# SCH_Bed_sensor_2021-08-20.net
KiCad netlist of a schematic drawn in EasyEDA
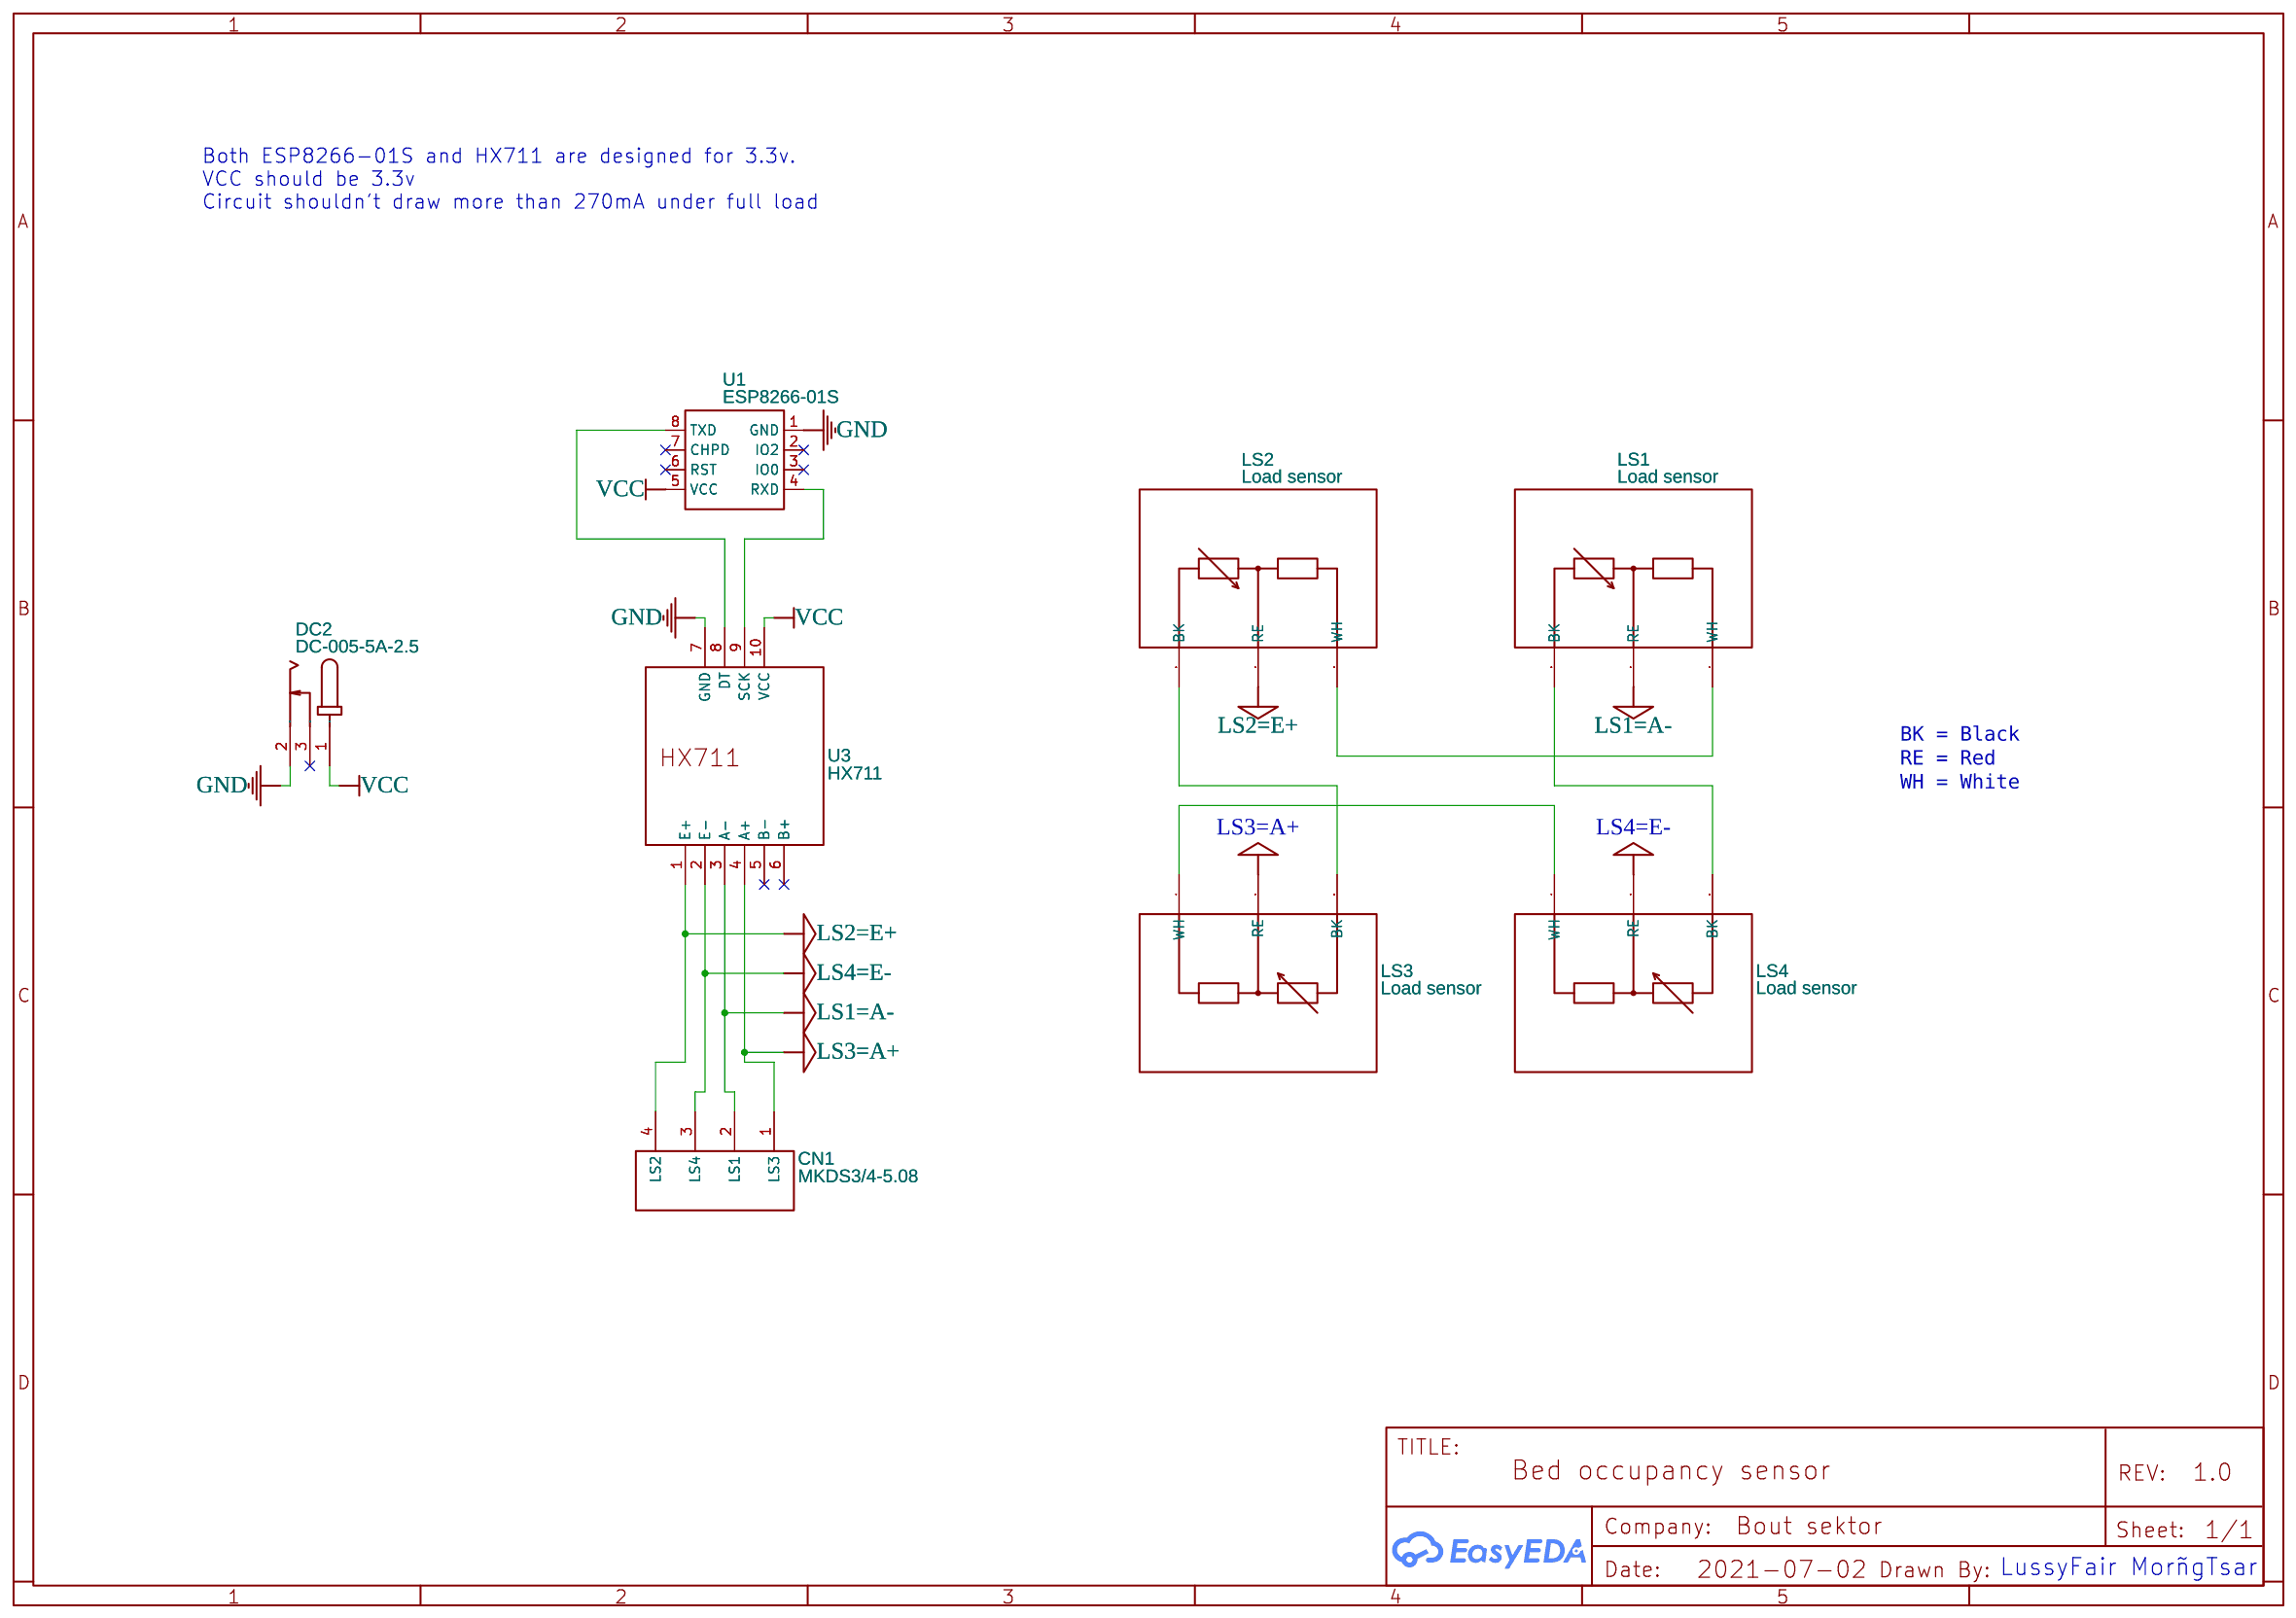
[diagram p0: schematic sheet]

(export (version "E")
  (design (tool "Eeschema 10.0.6"))
  (components
    (comp (ref "CN1")
      (value "MKDS3/4-5.08")
      (fields (field (name "BOM_Supplier Part") "C90087"))
      (libsource (lib "") (part "MKDS3/4-5.08"))
    )
    (comp (ref "DC2")
      (value "DC-005-5A-2.5")
      (fields (field (name "BOM_Supplier Part") "C381115"))
      (libsource (lib "") (part "DC-005-5A-2.5"))
    )
    (comp (ref "LS1") (value "Load sensor") (libsource (lib "") (part "Load sensor_1")))
    (comp (ref "LS2") (value "Load sensor") (libsource (lib "") (part "Load sensor_1")))
    (comp (ref "LS3") (value "Load sensor") (libsource (lib "") (part "Load sensor")))
    (comp (ref "LS4") (value "Load sensor") (libsource (lib "") (part "Load sensor")))
    (comp (ref "U1")
      (value "ESP8266-01S")
      (fields (field (name "BOM_Manufacturer Part") "ESP-01S") (field (name "BOM_Supplier Part") "C111009"))
      (libsource (lib "") (part "ESP8266-01S"))
    )
    (comp (ref "U3")
      (value "HX711")
      (fields (field (name "BOM_Supplier Part") "C43656"))
      (libsource (lib "") (part "HX711"))
    )
  )
  (nets
    (net (code "1") (name "GND") (class "Default")
      (node (ref "DC2") (pin "2") (pinfunction "2_2") (pintype "unspecified"))
      (node (ref "U1") (pin "1") (pinfunction "GND_1") (pintype "unspecified"))
      (node (ref "U3") (pin "7") (pinfunction "GND_7") (pintype "unspecified"))
    )
    (net (code "2") (name "LS1=A-") (class "Default")
      (node (ref "CN1") (pin "2") (pinfunction "LS1_2") (pintype "unspecified"))
      (node (ref "LS1") (pin "2") (pinfunction "RE_2") (pintype "unspecified"))
      (node (ref "U3") (pin "3") (pinfunction "A-_3") (pintype "unspecified"))
    )
    (net (code "3") (name "LS2=E+") (class "Default")
      (node (ref "CN1") (pin "4") (pinfunction "LS2_4") (pintype "unspecified"))
      (node (ref "LS2") (pin "2") (pinfunction "RE_2") (pintype "unspecified"))
      (node (ref "U3") (pin "1") (pinfunction "E+_1") (pintype "unspecified"))
    )
    (net (code "4") (name "LS3=A+") (class "Default")
      (node (ref "CN1") (pin "1") (pinfunction "LS3_1") (pintype "unspecified"))
      (node (ref "LS3") (pin "2") (pinfunction "RE_2") (pintype "unspecified"))
      (node (ref "U3") (pin "4") (pinfunction "A+_4") (pintype "unspecified"))
    )
    (net (code "5") (name "LS4=E-") (class "Default")
      (node (ref "CN1") (pin "3") (pinfunction "LS4_3") (pintype "unspecified"))
      (node (ref "LS4") (pin "2") (pinfunction "RE_2") (pintype "unspecified"))
      (node (ref "U3") (pin "2") (pinfunction "E-_2") (pintype "unspecified"))
    )
    (net (code "6") (name "Net-(LS1-BK)") (class "Default")
      (node (ref "LS1") (pin "3") (pinfunction "BK_3") (pintype "unspecified"))
      (node (ref "LS4") (pin "3") (pinfunction "BK_3") (pintype "unspecified"))
    )
    (net (code "7") (name "Net-(LS1-WH)") (class "Default")
      (node (ref "LS1") (pin "1") (pinfunction "WH_1") (pintype "unspecified"))
      (node (ref "LS2") (pin "1") (pinfunction "WH_1") (pintype "unspecified"))
    )
    (net (code "8") (name "Net-(LS2-BK)") (class "Default")
      (node (ref "LS2") (pin "3") (pinfunction "BK_3") (pintype "unspecified"))
      (node (ref "LS3") (pin "3") (pinfunction "BK_3") (pintype "unspecified"))
    )
    (net (code "9") (name "Net-(LS3-WH)") (class "Default")
      (node (ref "LS3") (pin "1") (pinfunction "WH_1") (pintype "unspecified"))
      (node (ref "LS4") (pin "1") (pinfunction "WH_1") (pintype "unspecified"))
    )
    (net (code "10") (name "Net-(U1-RXD)") (class "Default")
      (node (ref "U1") (pin "4") (pinfunction "RXD_4") (pintype "unspecified"))
      (node (ref "U3") (pin "9") (pinfunction "SCK_9") (pintype "unspecified"))
    )
    (net (code "11") (name "Net-(U1-TXD)") (class "Default")
      (node (ref "U1") (pin "8") (pinfunction "TXD_8") (pintype "unspecified"))
      (node (ref "U3") (pin "8") (pinfunction "DT_8") (pintype "unspecified"))
    )
    (net (code "12") (name "VCC") (class "Default")
      (node (ref "DC2") (pin "1") (pinfunction "1_1") (pintype "unspecified"))
      (node (ref "U1") (pin "5") (pinfunction "VCC_5") (pintype "unspecified"))
      (node (ref "U3") (pin "10") (pinfunction "VCC_10") (pintype "unspecified"))
    )
    (net (code "13") (name "unconnected-(DC2-Pad3)") (class "Default")
      (node (ref "DC2") (pin "3") (pinfunction "3_3") (pintype "unspecified+no_connect"))
    )
    (net (code "14") (name "unconnected-(U1-CHPD-Pad7)") (class "Default")
      (node (ref "U1") (pin "7") (pinfunction "CHPD_7") (pintype "unspecified+no_connect"))
    )
    (net (code "15") (name "unconnected-(U1-IO0-Pad3)") (class "Default")
      (node (ref "U1") (pin "3") (pinfunction "IO0_3") (pintype "unspecified+no_connect"))
    )
    (net (code "16") (name "unconnected-(U1-IO2-Pad2)") (class "Default")
      (node (ref "U1") (pin "2") (pinfunction "IO2_2") (pintype "unspecified+no_connect"))
    )
    (net (code "17") (name "unconnected-(U1-RST-Pad6)") (class "Default")
      (node (ref "U1") (pin "6") (pinfunction "RST_6") (pintype "unspecified+no_connect"))
    )
    (net (code "18") (name "unconnected-(U3-B+-Pad6)") (class "Default")
      (node (ref "U3") (pin "6") (pinfunction "B+_6") (pintype "unspecified+no_connect"))
    )
    (net (code "19") (name "unconnected-(U3-B--Pad5)") (class "Default")
      (node (ref "U3") (pin "5") (pinfunction "B-_5") (pintype "unspecified+no_connect"))
    )
  )
)
